# relaydriver.net
KiCad netlist of a schematic drawn in EAGLE
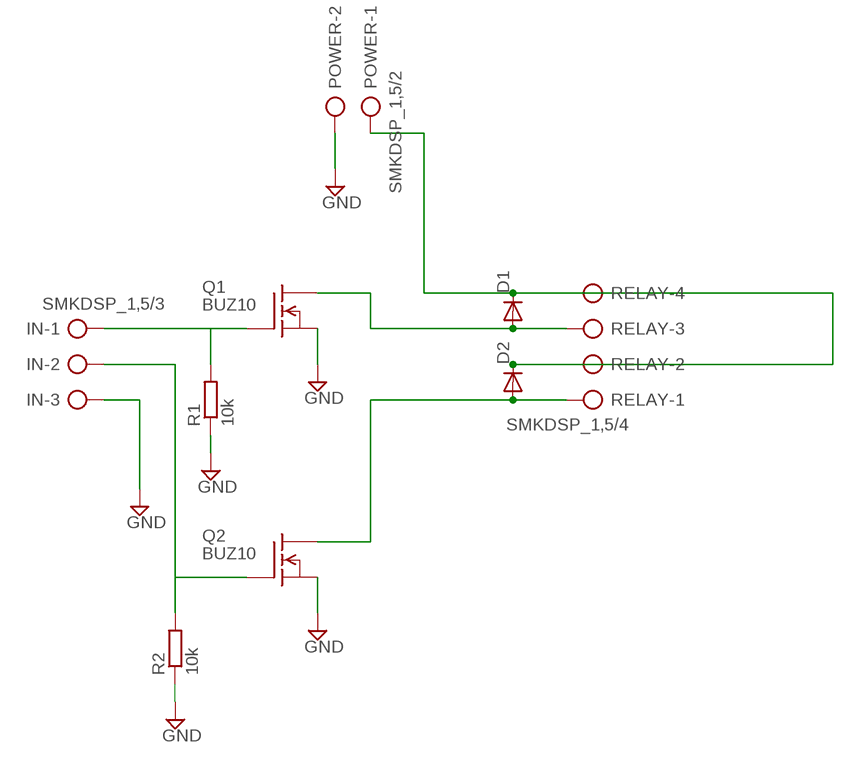
[diagram p0: schematic, sheet 1]

(export (version "E")
  (design (tool "Eeschema 10.0.6"))
  (components
    (comp (ref "D1")
      (value "DIODE-DO201-15")
      (footprint "eagle-import:DO201-15")
      (libsource (lib "eagle-import") (part "DIODE-DO201-15"))
    )
    (comp (ref "D2")
      (value "DIODE-DO201-15")
      (footprint "eagle-import:DO201-15")
      (libsource (lib "eagle-import") (part "DIODE-DO201-15"))
    )
    (comp (ref "IN")
      (value "SMKDSP_1,5/3")
      (footprint "eagle-import:SMKDSP_1,5_3")
      (fields (field (name "MF") "FARNELL") (field (name "MPN") "1733583"))
      (libsource (lib "eagle-import") (part "SMKDSP_1,5/3"))
    )
    (comp (ref "POWER")
      (value "SMKDSP_1,5/2")
      (footprint "eagle-import:SMKDSP_1,5_2")
      (fields (field (name "MF") "FARNELL") (field (name "MPN") "1733570"))
      (libsource (lib "eagle-import") (part "SMKDSP_1,5/2"))
    )
    (comp (ref "Q1")
      (value "BUZ10")
      (footprint "eagle-import:TO220")
      (libsource (lib "eagle-import") (part "BUZ10"))
    )
    (comp (ref "Q2")
      (value "BUZ10")
      (footprint "eagle-import:TO220")
      (libsource (lib "eagle-import") (part "BUZ10"))
    )
    (comp (ref "R1")
      (value "10k")
      (footprint "eagle-import:0207_10")
      (libsource (lib "eagle-import") (part "R-EU_0207/10"))
    )
    (comp (ref "R2")
      (value "10k")
      (footprint "eagle-import:0207_10")
      (libsource (lib "eagle-import") (part "R-EU_0207/10"))
    )
    (comp (ref "RELAY")
      (value "SMKDSP_1,5/4")
      (footprint "eagle-import:SMKDSP_1,5_4")
      (fields (field (name "MF") "FARNELL") (field (name "MPN") "1733596"))
      (libsource (lib "eagle-import") (part "SMKDSP_1,5/4"))
    )
  )
  (nets
    (net (code "1") (name "GND") (class "Default")
      (node (ref "IN") (pin "3") (pinfunction "KL_3") (pintype "passive"))
      (node (ref "POWER") (pin "2") (pinfunction "KL_2") (pintype "passive"))
      (node (ref "Q1") (pin "3") (pinfunction "S_3") (pintype "passive"))
      (node (ref "Q2") (pin "3") (pinfunction "S_3") (pintype "passive"))
      (node (ref "R1") (pin "1") (pinfunction "1_1") (pintype "passive"))
      (node (ref "R2") (pin "1") (pinfunction "1_1") (pintype "passive"))
    )
    (net (code "2") (name "Net-(INA-KL)") (class "Default")
      (node (ref "IN") (pin "1") (pinfunction "KL_1") (pintype "passive"))
      (node (ref "Q1") (pin "1") (pinfunction "G_1") (pintype "passive"))
      (node (ref "R1") (pin "2") (pinfunction "2_2") (pintype "passive"))
    )
    (net (code "3") (name "Net-(INB-KL)") (class "Default")
      (node (ref "IN") (pin "2") (pinfunction "KL_2") (pintype "passive"))
      (node (ref "Q2") (pin "1") (pinfunction "G_1") (pintype "passive"))
      (node (ref "R2") (pin "2") (pinfunction "2_2") (pintype "passive"))
    )
    (net (code "4") (name "Net-(POWERA-KL)") (class "Default")
      (node (ref "D1") (pin "C") (pinfunction "C_C") (pintype "passive"))
      (node (ref "D2") (pin "C") (pinfunction "C_C") (pintype "passive"))
      (node (ref "POWER") (pin "1") (pinfunction "KL_1") (pintype "passive"))
      (node (ref "RELAY") (pin "2") (pinfunction "KL_2") (pintype "passive"))
      (node (ref "RELAY") (pin "4") (pinfunction "KL_4") (pintype "passive"))
    )
    (net (code "5") (name "Net-(Q1-D)") (class "Default")
      (node (ref "D1") (pin "A") (pinfunction "A_A") (pintype "passive"))
      (node (ref "Q1") (pin "2") (pinfunction "D_2") (pintype "passive"))
      (node (ref "RELAY") (pin "3") (pinfunction "KL_3") (pintype "passive"))
    )
    (net (code "6") (name "Net-(Q2-D)") (class "Default")
      (node (ref "D2") (pin "A") (pinfunction "A_A") (pintype "passive"))
      (node (ref "Q2") (pin "2") (pinfunction "D_2") (pintype "passive"))
      (node (ref "RELAY") (pin "1") (pinfunction "KL_1") (pintype "passive"))
    )
  )
)
